# DesktopMini.net
KiCad netlist of a schematic drawn in EAGLE
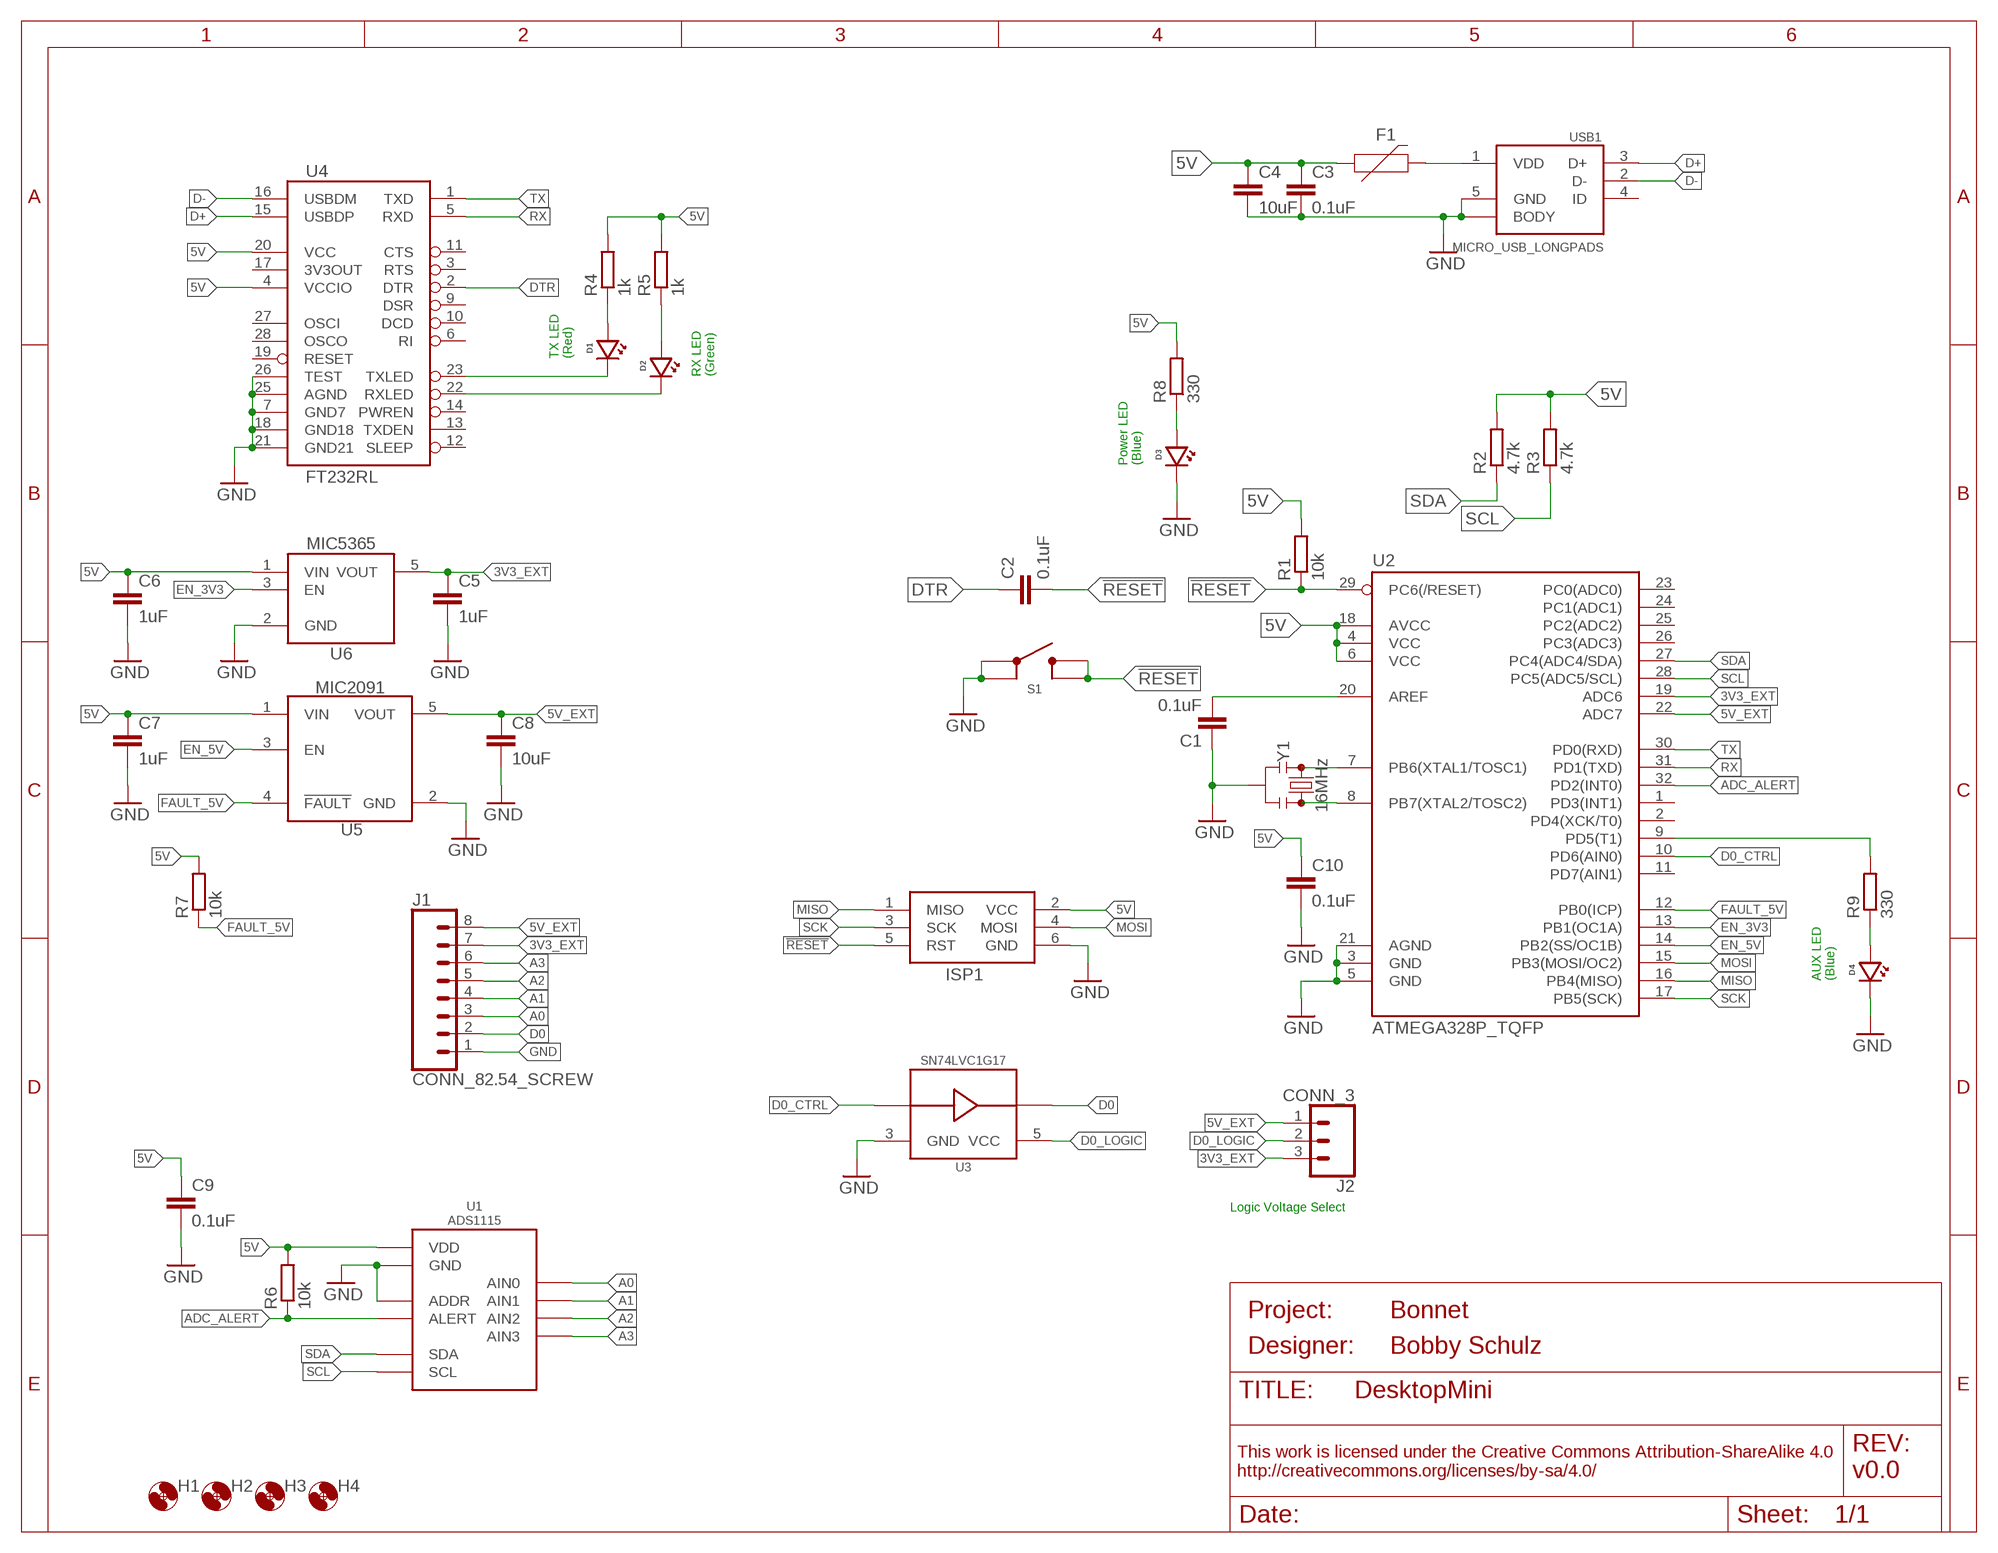
[diagram p0: schematic, sheet 1]

(export (version "E")
  (design (tool "Eeschema 10.0.6"))
  (components
    (comp (ref "C1")
      (value "0.1uF")
      (footprint "eagle-import:C0603")
      (fields (field (name "MF") "Murata") (field (name "MPN") "GCM188R71E104KA57D"))
      (libsource (lib "eagle-import") (part "C-EUC06030.1UF"))
    )
    (comp (ref "C2")
      (value "0.1uF")
      (footprint "eagle-import:C0603")
      (fields (field (name "MF") "Murata") (field (name "MPN") "GCM188R71E104KA57D"))
      (libsource (lib "eagle-import") (part "C-EUC06030.1UF"))
    )
    (comp (ref "C3")
      (value "0.1uF")
      (footprint "eagle-import:C0603")
      (fields (field (name "MF") "Murata") (field (name "MPN") "GCM188R71E104KA57D"))
      (libsource (lib "eagle-import") (part "C-EUC06030.1UF"))
    )
    (comp (ref "C4")
      (value "10uF")
      (footprint "eagle-import:C0805")
      (fields (field (name "MF") "Murata") (field (name "MPN") "GRM21BR61C106KE15K"))
      (libsource (lib "eagle-import") (part "C-EUC080510UF"))
    )
    (comp (ref "C5")
      (value "1uF")
      (footprint "eagle-import:C0603")
      (fields (field (name "MF") "Yaiyo Yuden") (field (name "MPN") "EMK107BJ105KA-T"))
      (libsource (lib "eagle-import") (part "C-EUC06031UF"))
    )
    (comp (ref "C6")
      (value "1uF")
      (footprint "eagle-import:C0603")
      (fields (field (name "MF") "Yaiyo Yuden") (field (name "MPN") "EMK107BJ105KA-T"))
      (libsource (lib "eagle-import") (part "C-EUC06031UF"))
    )
    (comp (ref "C7")
      (value "1uF")
      (footprint "eagle-import:C0603")
      (fields (field (name "MF") "Yaiyo Yuden") (field (name "MPN") "EMK107BJ105KA-T"))
      (libsource (lib "eagle-import") (part "C-EUC06031UF"))
    )
    (comp (ref "C8")
      (value "10uF")
      (footprint "eagle-import:C0805")
      (fields (field (name "MF") "Murata") (field (name "MPN") "GRM21BR61C106KE15K"))
      (libsource (lib "eagle-import") (part "C-EUC080510UF"))
    )
    (comp (ref "C9")
      (value "0.1uF")
      (footprint "eagle-import:C0603")
      (fields (field (name "MF") "Murata") (field (name "MPN") "GCM188R71E104KA57D"))
      (libsource (lib "eagle-import") (part "C-EUC06030.1UF"))
    )
    (comp (ref "C10")
      (value "0.1uF")
      (footprint "eagle-import:C0603")
      (fields (field (name "MF") "Murata") (field (name "MPN") "GCM188R71E104KA57D"))
      (libsource (lib "eagle-import") (part "C-EUC06030.1UF"))
    )
    (comp (ref "D1")
      (value "LEDRED0603")
      (footprint "eagle-import:LED_0603")
      (fields (field (name "MF") "Wurth") (field (name "MPN") "150060RS75000"))
      (libsource (lib "eagle-import") (part "LED0603RED"))
    )
    (comp (ref "D2")
      (value "LEDGREEN0603")
      (footprint "eagle-import:LED_0603")
      (fields (field (name "MF") "Wurth") (field (name "MPN") "150060GS75000"))
      (libsource (lib "eagle-import") (part "LED0603GREEN"))
    )
    (comp (ref "D3")
      (value "LEDBLUE0603")
      (footprint "eagle-import:LED_0603")
      (fields (field (name "MF") "Wurth") (field (name "MPN") "150060BS75000"))
      (libsource (lib "eagle-import") (part "LED0603BLUE"))
    )
    (comp (ref "D4")
      (value "LEDBLUE0603")
      (footprint "eagle-import:LED_0603")
      (fields (field (name "MF") "Wurth") (field (name "MPN") "150060BS75000"))
      (libsource (lib "eagle-import") (part "LED0603BLUE"))
    )
    (comp (ref "F1")
      (value "PPTC_HALF-AMP")
      (footprint "eagle-import:1206")
      (fields (field (name "MF") "Bourns") (field (name "MPN") "MF-NSMF020-2"))
      (libsource (lib "eagle-import") (part "PPTC_HALF-AMP"))
    )
    (comp (ref "H1")
      (value "MOUNTING_HOLE4_NP")
      (footprint "eagle-import:4_40")
      (fields (field (name "MPN") "DNP"))
      (libsource (lib "eagle-import") (part "MOUNTING_HOLE4_NP"))
    )
    (comp (ref "H2")
      (value "MOUNTING_HOLE4_NP")
      (footprint "eagle-import:4_40")
      (fields (field (name "MPN") "DNP"))
      (libsource (lib "eagle-import") (part "MOUNTING_HOLE4_NP"))
    )
    (comp (ref "H3")
      (value "MOUNTING_HOLE4_NP")
      (footprint "eagle-import:4_40")
      (fields (field (name "MPN") "DNP"))
      (libsource (lib "eagle-import") (part "MOUNTING_HOLE4_NP"))
    )
    (comp (ref "H4")
      (value "MOUNTING_HOLE4_NP")
      (footprint "eagle-import:4_40")
      (fields (field (name "MPN") "DNP"))
      (libsource (lib "eagle-import") (part "MOUNTING_HOLE4_NP"))
    )
    (comp (ref "ISP1")
      (value "AVRISP-6")
      (footprint "eagle-import:AVRISP")
      (libsource (lib "eagle-import") (part "AVRISP-6"))
    )
    (comp (ref "J1")
      (value "CONN_82.54_SCREW")
      (footprint "eagle-import:1X08_SCREW")
      (fields (field (name "MF") "On Shore") (field (name "MPN") "OSTVN08A150"))
      (libsource (lib "eagle-import") (part "CONN_82.54_SCREW"))
    )
    (comp (ref "J2")
      (value "CONN_3")
      (footprint "eagle-import:1X03")
      (libsource (lib "eagle-import") (part "CONN_3"))
    )
    (comp (ref "R1")
      (value "10k")
      (footprint "eagle-import:R0603")
      (fields (field (name "MF") "Yageo") (field (name "MPN") "RC0603FR-0710KL"))
      (libsource (lib "eagle-import") (part "R-EU_R060310K"))
    )
    (comp (ref "R2")
      (value "4.7k")
      (footprint "eagle-import:R0603")
      (fields (field (name "MF") "Yageo") (field (name "MPN") "RC0603FR-074K7L"))
      (libsource (lib "eagle-import") (part "R-EU_R06034.7K"))
    )
    (comp (ref "R3")
      (value "4.7k")
      (footprint "eagle-import:R0603")
      (fields (field (name "MF") "Yageo") (field (name "MPN") "RC0603FR-074K7L"))
      (libsource (lib "eagle-import") (part "R-EU_R06034.7K"))
    )
    (comp (ref "R4")
      (value "1k")
      (footprint "eagle-import:R0603")
      (fields (field (name "MF") "Yageo") (field (name "MPN") "AC0603FR-071KL"))
      (libsource (lib "eagle-import") (part "R-EU_R06031K"))
    )
    (comp (ref "R5")
      (value "1k")
      (footprint "eagle-import:R0603")
      (fields (field (name "MF") "Yageo") (field (name "MPN") "AC0603FR-071KL"))
      (libsource (lib "eagle-import") (part "R-EU_R06031K"))
    )
    (comp (ref "R6")
      (value "10k")
      (footprint "eagle-import:R0603")
      (fields (field (name "MF") "Yageo") (field (name "MPN") "RC0603FR-0710KL"))
      (libsource (lib "eagle-import") (part "R-EU_R060310K"))
    )
    (comp (ref "R7")
      (value "10k")
      (footprint "eagle-import:R0603")
      (fields (field (name "MF") "Yageo") (field (name "MPN") "RC0603FR-0710KL"))
      (libsource (lib "eagle-import") (part "R-EU_R060310K"))
    )
    (comp (ref "R8")
      (value "330")
      (footprint "eagle-import:R0603")
      (fields (field (name "MF") "Yageo") (field (name "MPN") "RC0603FR-07330RL"))
      (libsource (lib "eagle-import") (part "R-EU_R0603330"))
    )
    (comp (ref "R9")
      (value "330")
      (footprint "eagle-import:R0603")
      (fields (field (name "MF") "Yageo") (field (name "MPN") "RC0603FR-07330RL"))
      (libsource (lib "eagle-import") (part "R-EU_R0603330"))
    )
    (comp (ref "S1")
      (value "BUTTON6X6")
      (footprint "eagle-import:SWITCH_6MM")
      (libsource (lib "eagle-import") (part "BUTTON6X6"))
    )
    (comp (ref "U1")
      (value "ADS1115")
      (footprint "eagle-import:VSSOP_10")
      (fields (field (name "MF") "TI") (field (name "MPN") "ADS1115IDGSR"))
      (libsource (lib "eagle-import") (part "ADS1115"))
    )
    (comp (ref "U2")
      (value "ATMEGA328P_TQFP")
      (footprint "eagle-import:TQFP32-08")
      (fields (field (name "MF") "Atmel") (field (name "MPN") "ATMEGA328PB-AUR"))
      (libsource (lib "eagle-import") (part "ATMEGA328PTQFP_32"))
    )
    (comp (ref "U3")
      (value "SN74LVC1G17DCK")
      (footprint "eagle-import:DCK_R-PDSO-G5")
      (fields
        (field (name "DISP") "SN74LVC1G17")
        (field (name "MF") "TI")
        (field (name "MPN") "SN74LVC1G17DCKR")
      )
      (libsource (lib "eagle-import") (part "SN74LVC1G17DCK"))
    )
    (comp (ref "U4")
      (value "FT232RL")
      (footprint "eagle-import:SSOP28DB")
      (libsource (lib "eagle-import") (part "FT232RLSSOP"))
    )
    (comp (ref "U5")
      (value "MIC2091")
      (footprint "eagle-import:SOT23-5")
      (fields
        (field (name "DISP") "MIC2091")
        (field (name "MF") "Microchip")
        (field (name "MPN") "MIC2091-1YM5-TR")
      )
      (libsource (lib "eagle-import") (part "MIC2091"))
    )
    (comp (ref "U6")
      (value "MIC53653.3SC70")
      (footprint "eagle-import:DCK_R-PDSO-G5")
      (fields (field (name "MF") "Microchip") (field (name "MPN") "MIC5365-3.3YC5-TR"))
      (libsource (lib "eagle-import") (part "MIC5365SC703.3"))
    )
    (comp (ref "USB1")
      (value "MICRO_USB_LONGPADS")
      (footprint "eagle-import:10118194-0001LF_10118194-0001LF_LONGER_PADS")
      (fields (field (name "MF") "Amphenol") (field (name "MPN") "10118194-0001LF"))
      (libsource (lib "eagle-import") (part "MICRO_USB_LONGPADS"))
    )
    (comp (ref "Y1")
      (value "16MHz")
      (footprint "eagle-import:RESONATOR-SMD-3.2X1.3")
      (fields (field (name "MF") "Murata") (field (name "MPN") "CSTNE16M0V530000R0"))
      (libsource (lib "eagle-import") (part "RESONATORSMD_3.2X1.316MHZ"))
    )
  )
  (nets
    (net (code "1") (name "/~{RESET}") (class "Default")
      (node (ref "C2") (pin "2") (pinfunction "2_2") (pintype "passive"))
      (node (ref "ISP1") (pin "5") (pinfunction "RST_5") (pintype "output"))
      (node (ref "R1") (pin "1") (pinfunction "1_1") (pintype "passive"))
      (node (ref "S1") (pin "3") (pinfunction "3_3") (pintype "bidirectional"))
      (node (ref "S1") (pin "4") (pinfunction "4_4") (pintype "bidirectional"))
      (node (ref "U2") (pin "29") (pinfunction "PC6(/RESET)_29") (pintype "bidirectional"))
    )
    (net (code "2") (name "3V3_EXT") (class "Default")
      (node (ref "C5") (pin "1") (pinfunction "1_1") (pintype "passive"))
      (node (ref "J1") (pin "7") (pinfunction "7_7") (pintype "passive"))
      (node (ref "J2") (pin "3") (pinfunction "3_3") (pintype "passive"))
      (node (ref "U2") (pin "19") (pinfunction "ADC6_19") (pintype "bidirectional"))
      (node (ref "U6") (pin "5") (pinfunction "VOUT_5") (pintype "power_in"))
    )
    (net (code "3") (name "5V") (class "Default")
      (node (ref "C10") (pin "1") (pinfunction "1_1") (pintype "passive"))
      (node (ref "C3") (pin "1") (pinfunction "1_1") (pintype "passive"))
      (node (ref "C4") (pin "1") (pinfunction "1_1") (pintype "passive"))
      (node (ref "C6") (pin "1") (pinfunction "1_1") (pintype "passive"))
      (node (ref "C7") (pin "1") (pinfunction "1_1") (pintype "passive"))
      (node (ref "C9") (pin "1") (pinfunction "1_1") (pintype "passive"))
      (node (ref "F1") (pin "1") (pinfunction "1_1") (pintype "bidirectional"))
      (node (ref "ISP1") (pin "2") (pinfunction "VCC_2") (pintype "power_in"))
      (node (ref "R1") (pin "2") (pinfunction "2_2") (pintype "passive"))
      (node (ref "R2") (pin "2") (pinfunction "2_2") (pintype "passive"))
      (node (ref "R3") (pin "2") (pinfunction "2_2") (pintype "passive"))
      (node (ref "R4") (pin "2") (pinfunction "2_2") (pintype "passive"))
      (node (ref "R5") (pin "2") (pinfunction "2_2") (pintype "passive"))
      (node (ref "R6") (pin "2") (pinfunction "2_2") (pintype "passive"))
      (node (ref "R7") (pin "2") (pinfunction "2_2") (pintype "passive"))
      (node (ref "R8") (pin "2") (pinfunction "2_2") (pintype "passive"))
      (node (ref "U1") (pin "8") (pinfunction "VDD_8") (pintype "power_in"))
      (node (ref "U2") (pin "18") (pinfunction "AVCC_18") (pintype "bidirectional"))
      (node (ref "U2") (pin "4") (pinfunction "VCC_4") (pintype "bidirectional"))
      (node (ref "U2") (pin "6") (pinfunction "VCC_6") (pintype "bidirectional"))
      (node (ref "U4") (pin "20") (pinfunction "VCC_20") (pintype "power_in"))
      (node (ref "U4") (pin "4") (pinfunction "VCCIO_4") (pintype "power_in"))
      (node (ref "U5") (pin "1") (pinfunction "VIN_1") (pintype "power_in"))
      (node (ref "U6") (pin "1") (pinfunction "VIN_1") (pintype "power_in"))
    )
    (net (code "4") (name "5V_EXT") (class "Default")
      (node (ref "C8") (pin "1") (pinfunction "1_1") (pintype "passive"))
      (node (ref "J1") (pin "8") (pinfunction "8_8") (pintype "passive"))
      (node (ref "J2") (pin "1") (pinfunction "1_1") (pintype "passive"))
      (node (ref "U2") (pin "22") (pinfunction "ADC7_22") (pintype "bidirectional"))
      (node (ref "U5") (pin "5") (pinfunction "VOUT_5") (pintype "power_in"))
    )
    (net (code "5") (name "A0") (class "Default")
      (node (ref "J1") (pin "3") (pinfunction "3_3") (pintype "passive"))
      (node (ref "U1") (pin "4") (pinfunction "AIN0_4") (pintype "input"))
    )
    (net (code "6") (name "A1") (class "Default")
      (node (ref "J1") (pin "4") (pinfunction "4_4") (pintype "passive"))
      (node (ref "U1") (pin "5") (pinfunction "AIN1_5") (pintype "input"))
    )
    (net (code "7") (name "A2") (class "Default")
      (node (ref "J1") (pin "5") (pinfunction "5_5") (pintype "passive"))
      (node (ref "U1") (pin "6") (pinfunction "AIN2_6") (pintype "input"))
    )
    (net (code "8") (name "A3") (class "Default")
      (node (ref "J1") (pin "6") (pinfunction "6_6") (pintype "passive"))
      (node (ref "U1") (pin "7") (pinfunction "AIN3_7") (pintype "input"))
    )
    (net (code "9") (name "ADC_ALERT") (class "Default")
      (node (ref "R6") (pin "1") (pinfunction "1_1") (pintype "passive"))
      (node (ref "U1") (pin "2") (pinfunction "ALERT_2") (pintype "bidirectional"))
      (node (ref "U2") (pin "32") (pinfunction "PD2(INT0)_32") (pintype "bidirectional"))
    )
    (net (code "10") (name "D+") (class "Default")
      (node (ref "U4") (pin "15") (pinfunction "USBDP_15") (pintype "bidirectional"))
      (node (ref "USB1") (pin "3") (pinfunction "D+_3") (pintype "bidirectional"))
    )
    (net (code "11") (name "D-") (class "Default")
      (node (ref "U4") (pin "16") (pinfunction "USBDM_16") (pintype "bidirectional"))
      (node (ref "USB1") (pin "2") (pinfunction "D-_2") (pintype "bidirectional"))
    )
    (net (code "12") (name "D0") (class "Default")
      (node (ref "J1") (pin "2") (pinfunction "2_2") (pintype "passive"))
      (node (ref "U3") (pin "4") (pinfunction "Y_4") (pintype "output"))
    )
    (net (code "13") (name "D0_CTRL") (class "Default")
      (node (ref "U2") (pin "10") (pinfunction "PD6(AIN0)_10") (pintype "bidirectional"))
      (node (ref "U3") (pin "2") (pinfunction "A_2") (pintype "input"))
    )
    (net (code "14") (name "D0_LOGIC") (class "Default")
      (node (ref "J2") (pin "2") (pinfunction "2_2") (pintype "passive"))
      (node (ref "U3") (pin "5") (pinfunction "VCC_5") (pintype "power_in"))
    )
    (net (code "15") (name "DTR") (class "Default")
      (node (ref "C2") (pin "1") (pinfunction "1_1") (pintype "passive"))
      (node (ref "U4") (pin "2") (pinfunction "DTR_2") (pintype "output"))
    )
    (net (code "16") (name "EN_3V3") (class "Default")
      (node (ref "U2") (pin "13") (pinfunction "PB1(OC1A)_13") (pintype "bidirectional"))
      (node (ref "U6") (pin "3") (pinfunction "EN_3") (pintype "input"))
    )
    (net (code "17") (name "EN_5V") (class "Default")
      (node (ref "U2") (pin "14") (pinfunction "PB2(SS/OC1B)_14") (pintype "bidirectional"))
      (node (ref "U5") (pin "3") (pinfunction "EN_3") (pintype "input"))
    )
    (net (code "18") (name "FAULT_5V") (class "Default")
      (node (ref "R7") (pin "1") (pinfunction "1_1") (pintype "passive"))
      (node (ref "U2") (pin "12") (pinfunction "PB0(ICP)_12") (pintype "bidirectional"))
      (node (ref "U5") (pin "4") (pinfunction "~{FAULT}_4") (pintype "output"))
    )
    (net (code "19") (name "GND") (class "Default")
      (node (ref "C1") (pin "1") (pinfunction "1_1") (pintype "passive"))
      (node (ref "C10") (pin "2") (pinfunction "2_2") (pintype "passive"))
      (node (ref "C3") (pin "2") (pinfunction "2_2") (pintype "passive"))
      (node (ref "C4") (pin "2") (pinfunction "2_2") (pintype "passive"))
      (node (ref "C5") (pin "2") (pinfunction "2_2") (pintype "passive"))
      (node (ref "C6") (pin "2") (pinfunction "2_2") (pintype "passive"))
      (node (ref "C7") (pin "2") (pinfunction "2_2") (pintype "passive"))
      (node (ref "C8") (pin "2") (pinfunction "2_2") (pintype "passive"))
      (node (ref "C9") (pin "2") (pinfunction "2_2") (pintype "passive"))
      (node (ref "D3") (pin "CATHODE") (pinfunction "CATHODE_CATHODE") (pintype "power_in"))
      (node (ref "D4") (pin "CATHODE") (pinfunction "CATHODE_CATHODE") (pintype "power_in"))
      (node (ref "ISP1") (pin "6") (pinfunction "GND_6") (pintype "power_in"))
      (node (ref "J1") (pin "1") (pinfunction "1_1") (pintype "passive"))
      (node (ref "S1") (pin "1") (pinfunction "1_1") (pintype "bidirectional"))
      (node (ref "S1") (pin "2") (pinfunction "2_2") (pintype "bidirectional"))
      (node (ref "U1") (pin "1") (pinfunction "ADDR_1") (pintype "bidirectional"))
      (node (ref "U1") (pin "3") (pinfunction "GND_3") (pintype "power_in"))
      (node (ref "U2") (pin "21") (pinfunction "AGND_21") (pintype "bidirectional"))
      (node (ref "U2") (pin "3") (pinfunction "GND_3") (pintype "bidirectional"))
      (node (ref "U2") (pin "5") (pinfunction "GND_5") (pintype "bidirectional"))
      (node (ref "U3") (pin "3") (pinfunction "GND_3") (pintype "power_in"))
      (node (ref "U4") (pin "18") (pinfunction "GND18_18") (pintype "power_in"))
      (node (ref "U4") (pin "21") (pinfunction "GND21_21") (pintype "power_in"))
      (node (ref "U4") (pin "25") (pinfunction "AGND_25") (pintype "power_in"))
      (node (ref "U4") (pin "26") (pinfunction "TEST_26") (pintype "input"))
      (node (ref "U4") (pin "7") (pinfunction "GND7_7") (pintype "power_in"))
      (node (ref "U5") (pin "2") (pinfunction "GND_2") (pintype "power_in"))
      (node (ref "U6") (pin "2") (pinfunction "GND_2") (pintype "power_in"))
      (node (ref "USB1") (pin "5") (pinfunction "GND_5") (pintype "power_in"))
      (node (ref "USB1") (pin "BODY@1") (pinfunction "BODY_BODY@1") (pintype "bidirectional"))
      (node (ref "USB1") (pin "BODY@2") (pinfunction "BODY_BODY@2") (pintype "bidirectional"))
      (node (ref "USB1") (pin "BODY@3") (pinfunction "BODY_BODY@3") (pintype "bidirectional"))
      (node (ref "USB1") (pin "BODY@4") (pinfunction "BODY_BODY@4") (pintype "bidirectional"))
      (node (ref "USB1") (pin "BODY@7") (pinfunction "BODY_BODY@7") (pintype "bidirectional"))
      (node (ref "USB1") (pin "BODY@8") (pinfunction "BODY_BODY@8") (pintype "bidirectional"))
      (node (ref "Y1") (pin "2") (pinfunction "2_2") (pintype "passive"))
    )
    (net (code "20") (name "MISO") (class "Default")
      (node (ref "ISP1") (pin "1") (pinfunction "MISO_1") (pintype "input"))
      (node (ref "U2") (pin "16") (pinfunction "PB4(MISO)_16") (pintype "bidirectional"))
    )
    (net (code "21") (name "MOSI") (class "Default")
      (node (ref "ISP1") (pin "4") (pinfunction "MOSI_4") (pintype "output"))
      (node (ref "U2") (pin "15") (pinfunction "PB3(MOSI/OC2)_15") (pintype "bidirectional"))
    )
    (net (code "22") (name "Net-(D1-PadANODE)") (class "Default")
      (node (ref "D1") (pin "ANODE") (pinfunction "ANODE_ANODE") (pintype "power_in"))
      (node (ref "R4") (pin "1") (pinfunction "1_1") (pintype "passive"))
    )
    (net (code "23") (name "Net-(D2-PadANODE)") (class "Default")
      (node (ref "D2") (pin "ANODE") (pinfunction "ANODE_ANODE") (pintype "power_in"))
      (node (ref "R5") (pin "1") (pinfunction "1_1") (pintype "passive"))
    )
    (net (code "24") (name "Net-(D3-PadANODE)") (class "Default")
      (node (ref "D3") (pin "ANODE") (pinfunction "ANODE_ANODE") (pintype "power_in"))
      (node (ref "R8") (pin "1") (pinfunction "1_1") (pintype "passive"))
    )
    (net (code "25") (name "Net-(D4-PadANODE)") (class "Default")
      (node (ref "D4") (pin "ANODE") (pinfunction "ANODE_ANODE") (pintype "power_in"))
      (node (ref "R9") (pin "1") (pinfunction "1_1") (pintype "passive"))
    )
    (net (code "26") (name "Net-(U2-AREF)") (class "Default")
      (node (ref "C1") (pin "2") (pinfunction "2_2") (pintype "passive"))
      (node (ref "U2") (pin "20") (pinfunction "AREF_20") (pintype "bidirectional"))
    )
    (net (code "27") (name "Net-(U2-PB6(XTAL1{slash}TOSC1))") (class "Default")
      (node (ref "U2") (pin "7") (pinfunction "PB6(XTAL1/TOSC1)_7") (pintype "bidirectional"))
      (node (ref "Y1") (pin "1") (pinfunction "1_1") (pintype "passive"))
    )
    (net (code "28") (name "Net-(U2-PB7(XTAL2{slash}TOSC2))") (class "Default")
      (node (ref "U2") (pin "8") (pinfunction "PB7(XTAL2/TOSC2)_8") (pintype "bidirectional"))
      (node (ref "Y1") (pin "3") (pinfunction "3_3") (pintype "passive"))
    )
    (net (code "29") (name "Net-(U2-PD5(T1))") (class "Default")
      (node (ref "R9") (pin "2") (pinfunction "2_2") (pintype "passive"))
      (node (ref "U2") (pin "9") (pinfunction "PD5(T1)_9") (pintype "bidirectional"))
    )
    (net (code "30") (name "Net-(U4-RXLED)") (class "Default")
      (node (ref "D2") (pin "CATHODE") (pinfunction "CATHODE_CATHODE") (pintype "power_in"))
      (node (ref "U4") (pin "22") (pinfunction "RXLED_22") (pintype "input"))
    )
    (net (code "31") (name "Net-(U4-TXLED)") (class "Default")
      (node (ref "D1") (pin "CATHODE") (pinfunction "CATHODE_CATHODE") (pintype "power_in"))
      (node (ref "U4") (pin "23") (pinfunction "TXLED_23") (pintype "input"))
    )
    (net (code "32") (name "Net-(USB1-VDD)") (class "Default")
      (node (ref "F1") (pin "2") (pinfunction "2_2") (pintype "bidirectional"))
      (node (ref "USB1") (pin "1") (pinfunction "VDD_1") (pintype "power_in"))
    )
    (net (code "33") (name "RX") (class "Default")
      (node (ref "U2") (pin "31") (pinfunction "PD1(TXD)_31") (pintype "bidirectional"))
      (node (ref "U4") (pin "5") (pinfunction "RXD_5") (pintype "input"))
    )
    (net (code "34") (name "SCK") (class "Default")
      (node (ref "ISP1") (pin "3") (pinfunction "SCK_3") (pintype "output"))
      (node (ref "U2") (pin "17") (pinfunction "PB5(SCK)_17") (pintype "bidirectional"))
    )
    (net (code "35") (name "SCL") (class "Default")
      (node (ref "R3") (pin "1") (pinfunction "1_1") (pintype "passive"))
      (node (ref "U1") (pin "10") (pinfunction "SCL_10") (pintype "input"))
      (node (ref "U2") (pin "28") (pinfunction "PC5(ADC5/SCL)_28") (pintype "bidirectional"))
    )
    (net (code "36") (name "SDA") (class "Default")
      (node (ref "R2") (pin "1") (pinfunction "1_1") (pintype "passive"))
      (node (ref "U1") (pin "9") (pinfunction "SDA_9") (pintype "bidirectional"))
      (node (ref "U2") (pin "27") (pinfunction "PC4(ADC4/SDA)_27") (pintype "bidirectional"))
    )
    (net (code "37") (name "TX") (class "Default")
      (node (ref "U2") (pin "30") (pinfunction "PD0(RXD)_30") (pintype "bidirectional"))
      (node (ref "U4") (pin "1") (pinfunction "TXD_1") (pintype "output"))
    )
    (net (code "38") (name "unconnected-(U2-PC0(ADC0)-Pad23)") (class "Default")
      (node (ref "U2") (pin "23") (pinfunction "PC0(ADC0)_23") (pintype "bidirectional"))
    )
    (net (code "39") (name "unconnected-(U2-PC1(ADC1)-Pad24)") (class "Default")
      (node (ref "U2") (pin "24") (pinfunction "PC1(ADC1)_24") (pintype "bidirectional"))
    )
    (net (code "40") (name "unconnected-(U2-PC2(ADC2)-Pad25)") (class "Default")
      (node (ref "U2") (pin "25") (pinfunction "PC2(ADC2)_25") (pintype "bidirectional"))
    )
    (net (code "41") (name "unconnected-(U2-PC3(ADC3)-Pad26)") (class "Default")
      (node (ref "U2") (pin "26") (pinfunction "PC3(ADC3)_26") (pintype "bidirectional"))
    )
    (net (code "42") (name "unconnected-(U2-PD3(INT1)-Pad1)") (class "Default")
      (node (ref "U2") (pin "1") (pinfunction "PD3(INT1)_1") (pintype "bidirectional"))
    )
    (net (code "43") (name "unconnected-(U2-PD4(XCK{slash}T0)-Pad2)") (class "Default")
      (node (ref "U2") (pin "2") (pinfunction "PD4(XCK/T0)_2") (pintype "bidirectional"))
    )
    (net (code "44") (name "unconnected-(U2-PD7(AIN1)-Pad11)") (class "Default")
      (node (ref "U2") (pin "11") (pinfunction "PD7(AIN1)_11") (pintype "bidirectional"))
    )
    (net (code "45") (name "unconnected-(U4-3V3OUT-Pad17)") (class "Default")
      (node (ref "U4") (pin "17") (pinfunction "3V3OUT_17") (pintype "output"))
    )
    (net (code "46") (name "unconnected-(U4-CTS-Pad11)") (class "Default")
      (node (ref "U4") (pin "11") (pinfunction "CTS_11") (pintype "input"))
    )
    (net (code "47") (name "unconnected-(U4-DCD-Pad10)") (class "Default")
      (node (ref "U4") (pin "10") (pinfunction "DCD_10") (pintype "input"))
    )
    (net (code "48") (name "unconnected-(U4-DSR-Pad9)") (class "Default")
      (node (ref "U4") (pin "9") (pinfunction "DSR_9") (pintype "input"))
    )
    (net (code "49") (name "unconnected-(U4-OSCI-Pad27)") (class "Default")
      (node (ref "U4") (pin "27") (pinfunction "OSCI_27") (pintype "input"))
    )
    (net (code "50") (name "unconnected-(U4-OSCO-Pad28)") (class "Default")
      (node (ref "U4") (pin "28") (pinfunction "OSCO_28") (pintype "output"))
    )
    (net (code "51") (name "unconnected-(U4-PWREN-Pad14)") (class "Default")
      (node (ref "U4") (pin "14") (pinfunction "PWREN_14") (pintype "input"))
    )
    (net (code "52") (name "unconnected-(U4-RESET-Pad19)") (class "Default")
      (node (ref "U4") (pin "19") (pinfunction "RESET_19") (pintype "input"))
    )
    (net (code "53") (name "unconnected-(U4-RI-Pad6)") (class "Default")
      (node (ref "U4") (pin "6") (pinfunction "RI_6") (pintype "input"))
    )
    (net (code "54") (name "unconnected-(U4-RTS-Pad3)") (class "Default")
      (node (ref "U4") (pin "3") (pinfunction "RTS_3") (pintype "output"))
    )
    (net (code "55") (name "unconnected-(U4-SLEEP-Pad12)") (class "Default")
      (node (ref "U4") (pin "12") (pinfunction "SLEEP_12") (pintype "input"))
    )
    (net (code "56") (name "unconnected-(U4-TXDEN-Pad13)") (class "Default")
      (node (ref "U4") (pin "13") (pinfunction "TXDEN_13") (pintype "input"))
    )
    (net (code "57") (name "unconnected-(USB1-ID-Pad4)") (class "Default")
      (node (ref "USB1") (pin "4") (pinfunction "ID_4") (pintype "passive"))
    )
  )
)
